# induction_heater.net
KiCad netlist of a schematic drawn in EAGLE
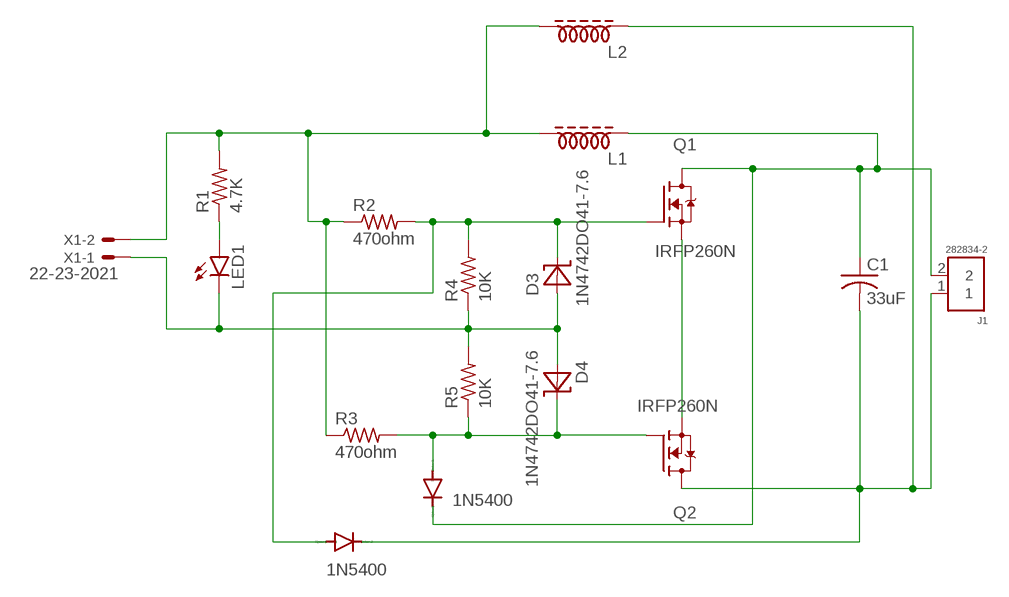
[diagram p0: schematic, sheet 1]

(export (version "E")
  (design (tool "Eeschema 10.0.6"))
  (components
    (comp (ref "C1")
      (value "33uF")
      (footprint "eagle-import:C150-054X183")
      (libsource (lib "eagle-import") (part "C-US150-054X183"))
    )
    (comp (ref "D1")
      (value "1N5400")
      (footprint "eagle-import:DO201-15")
      (libsource (lib "eagle-import") (part "1N5400"))
    )
    (comp (ref "D2")
      (value "1N5400")
      (footprint "eagle-import:DO201-15")
      (libsource (lib "eagle-import") (part "1N5400"))
    )
    (comp (ref "D3")
      (value "1N4742DO41-7.6")
      (footprint "eagle-import:DO41-7.6")
      (fields (field (name "MF") "EIC") (field (name "MP") "1N4742"))
      (libsource (lib "eagle-import") (part "1N4742DO41-7.6"))
    )
    (comp (ref "D4")
      (value "1N4742DO41-7.6")
      (footprint "eagle-import:DO41-7.6")
      (fields (field (name "MF") "EIC") (field (name "MP") "1N4742"))
      (libsource (lib "eagle-import") (part "1N4742DO41-7.6"))
    )
    (comp (ref "J1")
      (value "282834-2")
      (footprint "eagle-import:CONN_282834-2")
      (fields (field (name "MF") "TE Connectivity"))
      (libsource (lib "eagle-import") (part "282834-2"))
    )
    (comp (ref "L1")
      (value "Z14/40CCW")
      (footprint "eagle-import:Z15_4")
      (libsource (lib "eagle-import") (part "Z?CCW14/40"))
    )
    (comp (ref "L2")
      (value "Z14/40CCW")
      (footprint "eagle-import:Z15_4")
      (libsource (lib "eagle-import") (part "Z?CCW14/40"))
    )
    (comp (ref "LED1")
      (value "LED5MM")
      (footprint "eagle-import:LED5MM")
      (libsource (lib "eagle-import") (part "LED5MM"))
    )
    (comp (ref "Q1")
      (value "IRFP260N")
      (footprint "eagle-import:TO545P1560X500X2460-3")
      (fields (field (name "MF") "Infineon Technologies"))
      (libsource (lib "eagle-import") (part "IRFP260N"))
    )
    (comp (ref "Q2")
      (value "IRFP260N")
      (footprint "eagle-import:TO545P1560X500X2460-3")
      (fields (field (name "MF") "Infineon Technologies"))
      (libsource (lib "eagle-import") (part "IRFP260N"))
    )
    (comp (ref "R1")
      (value "4.7K")
      (footprint "eagle-import:0204_7")
      (libsource (lib "eagle-import") (part "R-US_0204/7"))
    )
    (comp (ref "R2")
      (value "470ohm")
      (footprint "eagle-import:0204_7")
      (libsource (lib "eagle-import") (part "R-US_0204/7"))
    )
    (comp (ref "R3")
      (value "470ohm")
      (footprint "eagle-import:0204_7")
      (libsource (lib "eagle-import") (part "R-US_0204/7"))
    )
    (comp (ref "R4")
      (value "10K")
      (footprint "eagle-import:0204_7")
      (libsource (lib "eagle-import") (part "R-US_0204/7"))
    )
    (comp (ref "R5")
      (value "10K")
      (footprint "eagle-import:0204_7")
      (libsource (lib "eagle-import") (part "R-US_0204/7"))
    )
    (comp (ref "X1")
      (value "22-23-2021")
      (footprint "eagle-import:22-23-2021")
      (fields (field (name "MF") "MOLEX"))
      (libsource (lib "eagle-import") (part "22-23-2021"))
    )
  )
  (nets
    (net (code "1") (name "Net-(LED1-C)") (class "Default")
      (node (ref "D3") (pin "A") (pinfunction "A_A") (pintype "passive"))
      (node (ref "D4") (pin "A") (pinfunction "A_A") (pintype "passive"))
      (node (ref "LED1") (pin "K") (pinfunction "C_K") (pintype "passive"))
      (node (ref "R4") (pin "1") (pinfunction "1_1") (pintype "passive"))
      (node (ref "R5") (pin "2") (pinfunction "2_2") (pintype "passive"))
      (node (ref "X1") (pin "1") (pinfunction "S_1") (pintype "passive"))
    )
    (net (code "2") (name "Net-(LED1-PadA)") (class "Default")
      (node (ref "LED1") (pin "A") (pinfunction "A_A") (pintype "passive"))
      (node (ref "R1") (pin "1") (pinfunction "1_1") (pintype "passive"))
    )
    (net (code "3") (name "Net-(Q1-D)") (class "Default")
      (node (ref "C1") (pin "1") (pinfunction "1_1") (pintype "passive"))
      (node (ref "D1") (pin "C") (pinfunction "C_C") (pintype "passive"))
      (node (ref "J1") (pin "2") (pinfunction "2_2") (pintype "passive"))
      (node (ref "L1") (pin "1") (pinfunction "1_1") (pintype "passive"))
      (node (ref "Q1") (pin "2") (pinfunction "D_2") (pintype "passive"))
    )
    (net (code "4") (name "Net-(Q1-G)") (class "Default")
      (node (ref "D2") (pin "A") (pinfunction "A_A") (pintype "passive"))
      (node (ref "D3") (pin "C") (pinfunction "C_C") (pintype "passive"))
      (node (ref "Q1") (pin "1") (pinfunction "G_1") (pintype "passive"))
      (node (ref "R2") (pin "2") (pinfunction "2_2") (pintype "passive"))
      (node (ref "R4") (pin "2") (pinfunction "2_2") (pintype "passive"))
    )
    (net (code "5") (name "Net-(Q1-S)") (class "Default")
      (node (ref "Q1") (pin "3") (pinfunction "S_3") (pintype "passive"))
      (node (ref "Q2") (pin "3") (pinfunction "S_3") (pintype "passive"))
    )
    (net (code "6") (name "Net-(Q2-D)") (class "Default")
      (node (ref "C1") (pin "2") (pinfunction "2_2") (pintype "passive"))
      (node (ref "D2") (pin "C") (pinfunction "C_C") (pintype "passive"))
      (node (ref "J1") (pin "1") (pinfunction "1_1") (pintype "passive"))
      (node (ref "L2") (pin "1") (pinfunction "1_1") (pintype "passive"))
      (node (ref "Q2") (pin "2") (pinfunction "D_2") (pintype "passive"))
    )
    (net (code "7") (name "Net-(Q2-G)") (class "Default")
      (node (ref "D1") (pin "A") (pinfunction "A_A") (pintype "passive"))
      (node (ref "D4") (pin "C") (pinfunction "C_C") (pintype "passive"))
      (node (ref "Q2") (pin "1") (pinfunction "G_1") (pintype "passive"))
      (node (ref "R3") (pin "2") (pinfunction "2_2") (pintype "passive"))
      (node (ref "R5") (pin "1") (pinfunction "1_1") (pintype "passive"))
    )
    (net (code "8") (name "Net-(X1B-S)") (class "Default")
      (node (ref "L1") (pin "2") (pinfunction "2_2") (pintype "passive"))
      (node (ref "L2") (pin "2") (pinfunction "2_2") (pintype "passive"))
      (node (ref "R1") (pin "2") (pinfunction "2_2") (pintype "passive"))
      (node (ref "R2") (pin "1") (pinfunction "1_1") (pintype "passive"))
      (node (ref "R3") (pin "1") (pinfunction "1_1") (pintype "passive"))
      (node (ref "X1") (pin "2") (pinfunction "S_2") (pintype "passive"))
    )
  )
)
